# SAMV71_Xplained_Ultra_CAN.net
KiCad netlist of a schematic drawn in Altium Designer
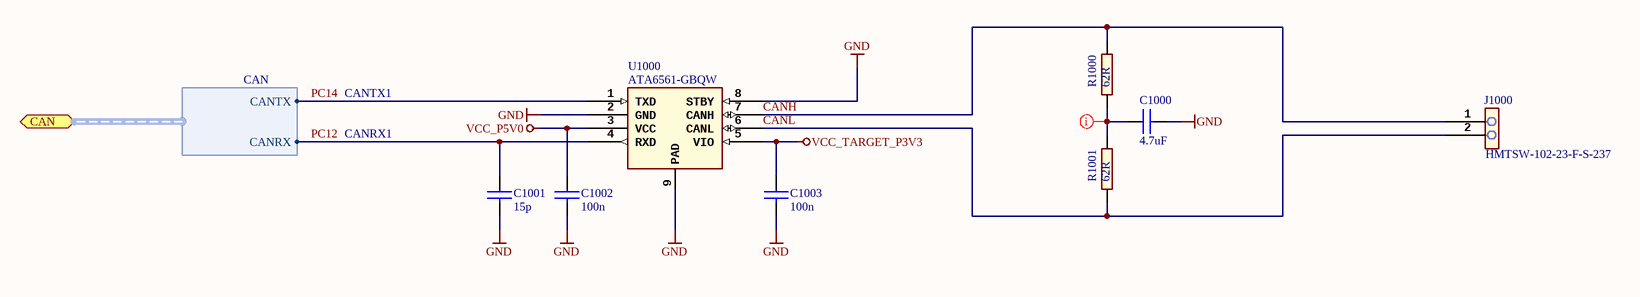
[diagram p0: SAMV71_Xplained_Ultra_CAN.SchDoc]

(export (version "E")
  (design (tool "Eeschema 10.0.6"))
  (components
    (comp (ref "C1000")
      (value "4.7uF")
      (footprint "AP1-00003")
      (description "Ceramic capacitor, SMD 0805, X5R, 25V, ±10 %")
      (fields (field (name "TOLERANCE") "Â±10%") (field (name "MANUFACTURER") "Murata"))
      (libsource (lib "AltiumDbLib") (part "CAP-NONPOL"))
    )
    (comp (ref "C1001")
      (value "15p")
      (footprint "AP1-00001")
      (description "Ceramic capacitor, SMD 0402, NP0, 50V, +/-5%")
      (fields (field (name "TOLERANCE") "50V, +/-5%"))
      (libsource (lib "AltiumDbLib") (part "CAP-NONPOL"))
    )
    (comp (ref "C1002")
      (value "100n")
      (footprint "AP1-00001")
      (description "Ceramic capacitor, SMD 0402, X7R, 16V, +/-10%")
      (fields (field (name "TOLERANCE") "16V, +/-10%") (field (name "MANUFACTURER") "Kemet"))
      (libsource (lib "AltiumDbLib") (part "CAP-NONPOL"))
    )
    (comp (ref "C1003")
      (value "100n")
      (footprint "AP1-00001")
      (description "Ceramic capacitor, SMD 0402, X7R, 16V, +/-10%")
      (fields (field (name "TOLERANCE") "16V, +/-10%") (field (name "MANUFACTURER") "Kemet"))
      (libsource (lib "AltiumDbLib") (part "CAP-NONPOL"))
    )
    (comp (ref "J1000")
      (value "HMTSW-102-23-F-S-237")
      (footprint "AP8-00733")
      (description "1x2 pin header, 2.54mm pitch, Pin-in-Paste THM")
      (fields (field (name "MANUFACTURER") "SAMTEC"))
      (libsource (lib "AltiumDbLib") (part "HEADER 1x2"))
    )
    (comp (ref "R1000")
      (value "62R")
      (footprint "AP2-00008")
      (description "Thick film resistor, SMD 1210, 0.5W, 1%")
      (fields (field (name "TOLERANCE") "1%") (field (name "Comment") "Generic component"))
      (libsource (lib "AltiumDbLib") (part "R2"))
    )
    (comp (ref "R1001")
      (value "62R")
      (footprint "AP2-00008")
      (description "Thick film resistor, SMD 1210, 0.5W, 1%")
      (fields (field (name "TOLERANCE") "1%") (field (name "Comment") "Generic component"))
      (libsource (lib "AltiumDbLib") (part "R2"))
    )
    (comp (ref "U1000")
      (value "ATA6561-GBQW")
      (footprint "AP6-00407")
      (description "5Mbit/s CAN Trasceiver,VCC = 5V, VIO = 2.8-5V, 3x3 mm VDFN8")
      (fields (field (name "MANUFACTURER") "ATMEL"))
      (libsource (lib "AltiumDbLib") (part "ATA6561"))
    )
  )
  (nets
    (net (code "2") (name "/CANH") (class "Default")
      (node (ref "J1000") (pin "1") (pinfunction "1_1") (pintype "passive"))
      (node (ref "R1000") (pin "2") (pinfunction "2_2") (pintype "passive"))
      (node (ref "U1000") (pin "7") (pinfunction "CANH_7") (pintype "bidirectional"))
    )
    (net (code "3") (name "/CANL") (class "Default")
      (node (ref "J1000") (pin "2") (pinfunction "2_2") (pintype "passive"))
      (node (ref "R1001") (pin "1") (pinfunction "1_1") (pintype "passive"))
      (node (ref "U1000") (pin "6") (pinfunction "CANL_6") (pintype "bidirectional"))
    )
    (net (code "4") (name "/PC12") (class "Default")
      (node (ref "C1001") (pin "1") (pinfunction "1_1") (pintype "passive"))
      (node (ref "U1000") (pin "4") (pinfunction "RXD_4") (pintype "output"))
    )
    (net (code "5") (name "/PC14") (class "Default")
      (node (ref "U1000") (pin "1") (pinfunction "TXD_1") (pintype "input"))
    )
    (net (code "7") (name "GND") (class "Default")
      (node (ref "C1000") (pin "2") (pinfunction "2_2") (pintype "passive"))
      (node (ref "C1001") (pin "2") (pinfunction "2_2") (pintype "passive"))
      (node (ref "C1002") (pin "2") (pinfunction "2_2") (pintype "passive"))
      (node (ref "C1003") (pin "2") (pinfunction "2_2") (pintype "passive"))
      (node (ref "U1000") (pin "2") (pinfunction "GND_2") (pintype "power_in"))
      (node (ref "U1000") (pin "8") (pinfunction "STBY_8") (pintype "input"))
      (node (ref "U1000") (pin "9") (pinfunction "PAD_9") (pintype "power_in"))
    )
    (net (code "8") (name "Net-(C1000-Pad1)") (class "Default")
      (node (ref "C1000") (pin "1") (pinfunction "1_1") (pintype "passive"))
      (node (ref "R1000") (pin "1") (pinfunction "1_1") (pintype "passive"))
      (node (ref "R1001") (pin "2") (pinfunction "2_2") (pintype "passive"))
    )
    (net (code "9") (name "VCC_P5V0") (class "Default")
      (node (ref "C1002") (pin "1") (pinfunction "1_1") (pintype "passive"))
      (node (ref "U1000") (pin "3") (pinfunction "VCC_3") (pintype "power_in"))
    )
    (net (code "10") (name "VCC_TARGET_P3V3") (class "Default")
      (node (ref "C1003") (pin "1") (pinfunction "1_1") (pintype "passive"))
      (node (ref "U1000") (pin "5") (pinfunction "VIO_5") (pintype "input"))
    )
  )
)
